# Gas_Sampler-GPS.net
KiCad netlist of a schematic drawn in Altium Designer
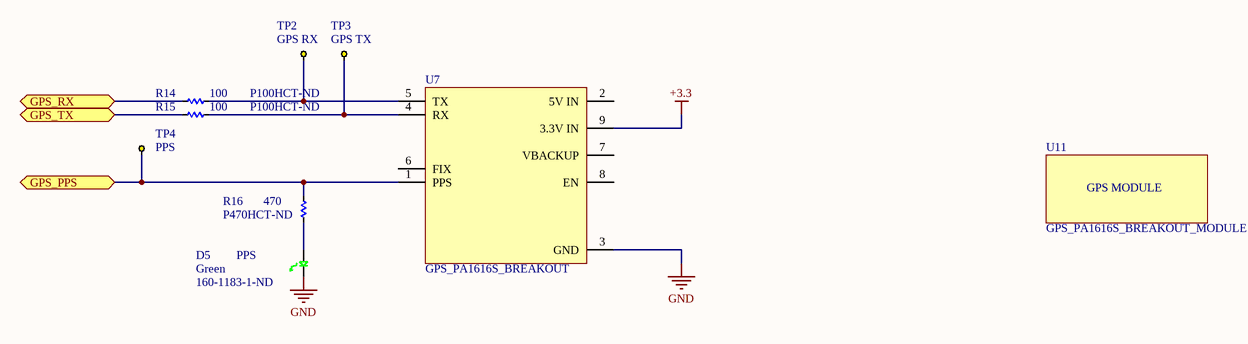
[diagram p0: Gas_Sampler-GPS.SchDoc]

(export (version "E")
  (design (tool "Eeschema 10.0.6"))
  (components
    (comp (ref "D5")
      (value "PPS")
      (footprint "LED_0603_GREEN")
      (description "LED GREEN CLEAR 0603 SMD")
      (fields
        (field (name "MANUFACTURER") "Lite-On Inc")
        (field (name "MANUFACTURER PART NUMBER") "LTST-C190GKT")
        (field (name "COLOR") "Green")
        (field (name "SUPPLIER PART NUMBER 1") "160-1183-1-ND")
      )
      (libsource (lib "diode") (part "LED_0603_GREEN_LG_LTST-C190GKT"))
    )
    (comp (ref "R14")
      (value "100")
      (footprint "R0603")
      (description "RES 100 OHM 1/10W 1% 0603 SMD")
      (fields
        (field (name "MANUFACTURER") "Panasonic Electronic Components")
        (field (name "MANUFACTURER PART NUMBER") "ERJ-3EKF1000V")
        (field (name "SUPPLIER PART NUMBER 1") "P100HCT-ND")
      )
      (libsource (lib "resistor") (part "RES_0603_100_OHM_1/10W_1%"))
    )
    (comp (ref "R15")
      (value "100")
      (footprint "R0603")
      (description "RES 100 OHM 1/10W 1% 0603 SMD")
      (fields
        (field (name "MANUFACTURER") "Panasonic Electronic Components")
        (field (name "MANUFACTURER PART NUMBER") "ERJ-3EKF1000V")
        (field (name "SUPPLIER PART NUMBER 1") "P100HCT-ND")
      )
      (libsource (lib "resistor") (part "RES_0603_100_OHM_1/10W_1%"))
    )
    (comp (ref "R16")
      (value "470")
      (footprint "R0603")
      (description "RES 470 OHM 1/10W 1% 0603 SMD")
      (fields
        (field (name "MANUFACTURER") "Panasonic Electronic Components")
        (field (name "MANUFACTURER PART NUMBER") "ERJ-3EKF4700V")
        (field (name "SUPPLIER PART NUMBER 1") "P470HCT-ND")
      )
      (libsource (lib "resistor") (part "RES_0603_470_OHM_1/10W_1%"))
    )
    (comp (ref "TP2")
      (value "GPS RX")
      (footprint "TP_KEYSTONE_5001")
      (description "PC TEST POINT TH RING")
      (fields
        (field (name "MANUFACTURER") "Keystone Electronics")
        (field (name "MANUFACTURER PART NUMBER") "5001")
      )
      (libsource (lib "miscellaneous") (part "TEST_KEYSTONE5001"))
    )
    (comp (ref "TP3")
      (value "GPS TX")
      (footprint "TP_KEYSTONE_5001")
      (description "PC TEST POINT TH RING")
      (fields
        (field (name "MANUFACTURER") "Keystone Electronics")
        (field (name "MANUFACTURER PART NUMBER") "5001")
      )
      (libsource (lib "miscellaneous") (part "TEST_KEYSTONE5001"))
    )
    (comp (ref "TP4")
      (value "PPS")
      (footprint "TP_KEYSTONE_5001")
      (description "PC TEST POINT TH RING")
      (fields
        (field (name "MANUFACTURER") "Keystone Electronics")
        (field (name "MANUFACTURER PART NUMBER") "5001")
      )
      (libsource (lib "miscellaneous") (part "TEST_KEYSTONE5001"))
    )
    (comp (ref "U7")
      (value "GPS_PA1616S_BREAKOUT")
      (footprint "HEADER_1X9_POS_UNSHROUDED")
      (description "Adafruit Ultimate GPS Breakout - 66 channel w/10 Hz updates - PA1616S")
      (libsource (lib "modules") (part "GPS_PA1616S_BREAKOUT"))
    )
    (comp (ref "U11")
      (value "GPS_PA1616S_BREAKOUT_MODULE")
      (footprint "GPS_PA1616S_BREAKOUT")
      (description "Adafruit Ultimate GPS Breakout - 66 channel w/10 Hz updates - PA1616S")
      (libsource (lib "modules") (part "GPS_PA1616S_BREAKOUT_MODULE"))
    )
  )
  (nets
    (net (code "1") (name "+3.3") (class "Default")
      (node (ref "U7") (pin "9") (pinfunction "3.3V_IN_9") (pintype "passive"))
    )
    (net (code "2") (name "/GPS_PPS") (class "Default")
      (node (ref "R16") (pin "2") (pintype "passive"))
      (node (ref "TP4") (pin "1") (pintype "passive"))
      (node (ref "U7") (pin "1") (pinfunction "PPS_1") (pintype "passive"))
    )
    (net (code "3") (name "/GPS_RX") (class "Default") (node (ref "R14") (pin "1") (pintype "passive")))
    (net (code "4") (name "/GPS_TX") (class "Default") (node (ref "R15") (pin "1") (pintype "passive")))
    (net (code "5") (name "GND") (class "Default")
      (node (ref "D5") (pin "2") (pinfunction "CATHODE_2") (pintype "passive"))
      (node (ref "U7") (pin "3") (pinfunction "GND_3") (pintype "passive"))
    )
    (net (code "6") (name "Net-(D5-ANODE)") (class "Default")
      (node (ref "D5") (pin "1") (pinfunction "ANODE_1") (pintype "passive"))
      (node (ref "R16") (pin "1") (pintype "passive"))
    )
    (net (code "7") (name "Net-(U7-RX)") (class "Default")
      (node (ref "R15") (pin "2") (pintype "passive"))
      (node (ref "TP3") (pin "1") (pintype "passive"))
      (node (ref "U7") (pin "4") (pinfunction "RX_4") (pintype "passive"))
    )
    (net (code "8") (name "Net-(U7-TX)") (class "Default")
      (node (ref "R14") (pin "2") (pintype "passive"))
      (node (ref "TP2") (pin "1") (pintype "passive"))
      (node (ref "U7") (pin "5") (pinfunction "TX_5") (pintype "passive"))
    )
    (net (code "9") (name "unconnected-(U7-5V_IN-Pad2)") (class "Default")
      (node (ref "U7") (pin "2") (pinfunction "5V_IN_2") (pintype "passive"))
    )
    (net (code "10") (name "unconnected-(U7-EN-Pad8)") (class "Default")
      (node (ref "U7") (pin "8") (pinfunction "EN_8") (pintype "passive"))
    )
    (net (code "11") (name "unconnected-(U7-FIX-Pad6)") (class "Default")
      (node (ref "U7") (pin "6") (pinfunction "FIX_6") (pintype "passive"))
    )
    (net (code "12") (name "unconnected-(U7-VBACKUP-Pad7)") (class "Default")
      (node (ref "U7") (pin "7") (pinfunction "VBACKUP_7") (pintype "passive"))
    )
  )
)
